# bistable-switch.net
KiCad netlist of a schematic drawn in EAGLE
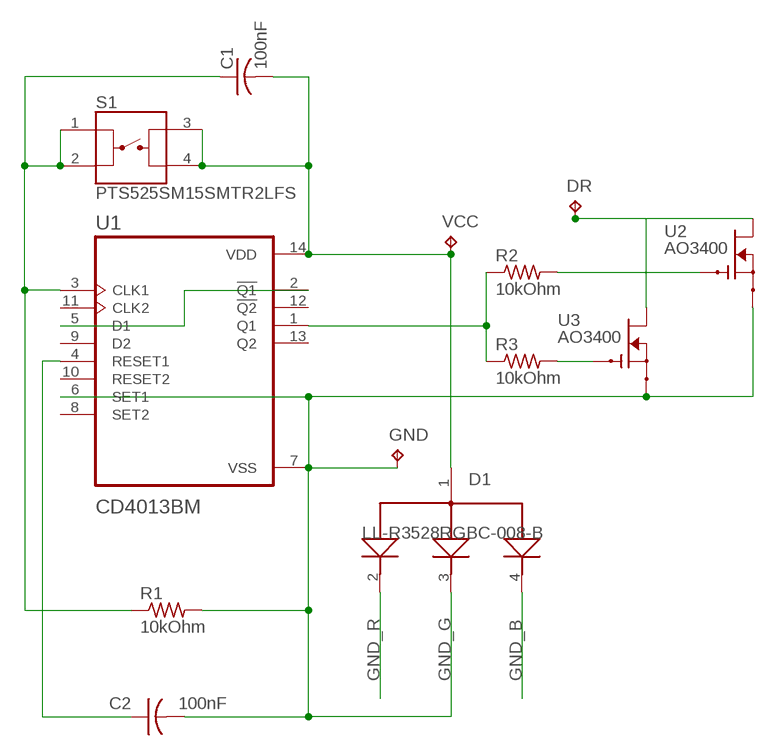
[diagram p0: schematic, sheet 1]

(export (version "E")
  (design (tool "Eeschema 10.0.6"))
  (components
    (comp (ref "C1")
      (value "100nF")
      (footprint "eagle-import:C0805")
      (libsource (lib "eagle-import") (part "C-USC0805"))
    )
    (comp (ref "C2")
      (value "100nF")
      (footprint "eagle-import:C0805")
      (libsource (lib "eagle-import") (part "C-USC0805"))
    )
    (comp (ref "D1")
      (value "LL-R3528RGBC-008-B")
      (footprint "eagle-import:LED_LL-R3528RGBC-008-B")
      (fields (field (name "MF") "Lucky Light"))
      (libsource (lib "eagle-import") (part "LL-R3528RGBC-008-B"))
    )
    (comp (ref "DR")
      (value "TPB1,27")
      (footprint "eagle-import:B1,27")
      (libsource (lib "eagle-import") (part "TPB1,27"))
    )
    (comp (ref "GND")
      (value "TPB1,27")
      (footprint "eagle-import:B1,27")
      (libsource (lib "eagle-import") (part "TPB1,27"))
    )
    (comp (ref "R1")
      (value "10kOhm")
      (footprint "eagle-import:R0805")
      (libsource (lib "eagle-import") (part "R-US_R0805"))
    )
    (comp (ref "R2")
      (value "10kOhm")
      (footprint "eagle-import:R0805")
      (libsource (lib "eagle-import") (part "R-US_R0805"))
    )
    (comp (ref "R3")
      (value "10kOhm")
      (footprint "eagle-import:R0805")
      (libsource (lib "eagle-import") (part "R-US_R0805"))
    )
    (comp (ref "S1")
      (value "PTS525SM15SMTR2LFS")
      (footprint "eagle-import:SW_PTS525SM15SMTR2LFS")
      (fields (field (name "MF") "C&K"))
      (libsource (lib "eagle-import") (part "PTS525SM15SMTR2LFS"))
    )
    (comp (ref "U1")
      (value "CD4013BM")
      (footprint "eagle-import:SOIC127P600X175-14N")
      (fields (field (name "MF") "Texas Instruments"))
      (libsource (lib "eagle-import") (part "CD4013BM"))
    )
    (comp (ref "U2")
      (value "AO3400")
      (footprint "eagle-import:SOT23")
      (fields (field (name "MF") "Alpha &"))
      (libsource (lib "eagle-import") (part "AO3400"))
    )
    (comp (ref "U3")
      (value "AO3400")
      (footprint "eagle-import:SOT23")
      (fields (field (name "MF") "Alpha &"))
      (libsource (lib "eagle-import") (part "AO3400"))
    )
    (comp (ref "VCC")
      (value "TPB1,27")
      (footprint "eagle-import:B1,27")
      (libsource (lib "eagle-import") (part "TPB1,27"))
    )
  )
  (nets
    (net (code "1") (name "/GND_B") (class "Default")
      (node (ref "D1") (pin "4") (pinfunction "CATHODE_BLUE_4") (pintype "passive"))
    )
    (net (code "2") (name "/GND_G") (class "Default")
      (node (ref "C2") (pin "2") (pinfunction "2_2") (pintype "passive"))
      (node (ref "D1") (pin "3") (pinfunction "CATHODE_GREEN_3") (pintype "passive"))
      (node (ref "GND") (pin "TP") (pinfunction "TP_TP") (pintype "input"))
      (node (ref "R1") (pin "2") (pinfunction "2_2") (pintype "passive"))
      (node (ref "U1") (pin "6") (pinfunction "SET1_6") (pintype "input"))
      (node (ref "U1") (pin "7") (pinfunction "VSS_7") (pintype "power_in"))
      (node (ref "U2") (pin "2") (pinfunction "S_2") (pintype "passive"))
      (node (ref "U3") (pin "2") (pinfunction "S_2") (pintype "passive"))
    )
    (net (code "3") (name "/GND_R") (class "Default")
      (node (ref "D1") (pin "2") (pinfunction "CATHODE_RED_2") (pintype "passive"))
    )
    (net (code "4") (name "Net-(D1-COMM_ANODE)") (class "Default")
      (node (ref "C1") (pin "2") (pinfunction "2_2") (pintype "passive"))
      (node (ref "D1") (pin "1") (pinfunction "COMM_ANODE_1") (pintype "passive"))
      (node (ref "S1") (pin "3") (pinfunction "3_3") (pintype "passive"))
      (node (ref "S1") (pin "4") (pinfunction "4_4") (pintype "passive"))
      (node (ref "U1") (pin "14") (pinfunction "VDD_14") (pintype "power_in"))
      (node (ref "VCC") (pin "TP") (pinfunction "TP_TP") (pintype "input"))
    )
    (net (code "5") (name "Net-(U1-CLK1)") (class "Default")
      (node (ref "C1") (pin "1") (pinfunction "1_1") (pintype "passive"))
      (node (ref "R1") (pin "1") (pinfunction "1_1") (pintype "passive"))
      (node (ref "S1") (pin "1") (pinfunction "1_1") (pintype "passive"))
      (node (ref "S1") (pin "2") (pinfunction "2_2") (pintype "passive"))
      (node (ref "U1") (pin "3") (pinfunction "CLK1_3") (pintype "input"))
    )
    (net (code "6") (name "Net-(U1-D1)") (class "Default")
      (node (ref "U1") (pin "2") (pinfunction "~{Q1}_2") (pintype "output"))
      (node (ref "U1") (pin "5") (pinfunction "D1_5") (pintype "input"))
    )
    (net (code "7") (name "Net-(U1-Q1)") (class "Default")
      (node (ref "R2") (pin "1") (pinfunction "1_1") (pintype "passive"))
      (node (ref "R3") (pin "1") (pinfunction "1_1") (pintype "passive"))
      (node (ref "U1") (pin "1") (pinfunction "Q1_1") (pintype "output"))
    )
    (net (code "8") (name "Net-(U1-RESET1)") (class "Default")
      (node (ref "C2") (pin "1") (pinfunction "1_1") (pintype "passive"))
      (node (ref "U1") (pin "4") (pinfunction "RESET1_4") (pintype "input"))
    )
    (net (code "9") (name "Net-(U2-D)") (class "Default")
      (node (ref "DR") (pin "TP") (pinfunction "TP_TP") (pintype "input"))
      (node (ref "U2") (pin "3") (pinfunction "D_3") (pintype "passive"))
      (node (ref "U3") (pin "3") (pinfunction "D_3") (pintype "passive"))
    )
    (net (code "10") (name "Net-(U2-G)") (class "Default")
      (node (ref "R2") (pin "2") (pinfunction "2_2") (pintype "passive"))
      (node (ref "U2") (pin "1") (pinfunction "G_1") (pintype "passive"))
    )
    (net (code "11") (name "Net-(U3-G)") (class "Default")
      (node (ref "R3") (pin "2") (pinfunction "2_2") (pintype "passive"))
      (node (ref "U3") (pin "1") (pinfunction "G_1") (pintype "passive"))
    )
    (net (code "12") (name "unconnected-(U1-CLK2-Pad11)") (class "Default")
      (node (ref "U1") (pin "11") (pinfunction "CLK2_11") (pintype "input"))
    )
    (net (code "13") (name "unconnected-(U1-D2-Pad9)") (class "Default")
      (node (ref "U1") (pin "9") (pinfunction "D2_9") (pintype "input"))
    )
    (net (code "14") (name "unconnected-(U1-Q2-Pad13)") (class "Default")
      (node (ref "U1") (pin "13") (pinfunction "Q2_13") (pintype "output"))
    )
    (net (code "15") (name "unconnected-(U1-RESET2-Pad10)") (class "Default")
      (node (ref "U1") (pin "10") (pinfunction "RESET2_10") (pintype "input"))
    )
    (net (code "16") (name "unconnected-(U1-SET2-Pad8)") (class "Default")
      (node (ref "U1") (pin "8") (pinfunction "SET2_8") (pintype "input"))
    )
    (net (code "17") (name "unconnected-(U1-~{Q2}-Pad12)") (class "Default")
      (node (ref "U1") (pin "12") (pinfunction "~{Q2}_12") (pintype "output"))
    )
  )
)
